# USB_to_UART.net
KiCad netlist of a schematic drawn in Altium Designer
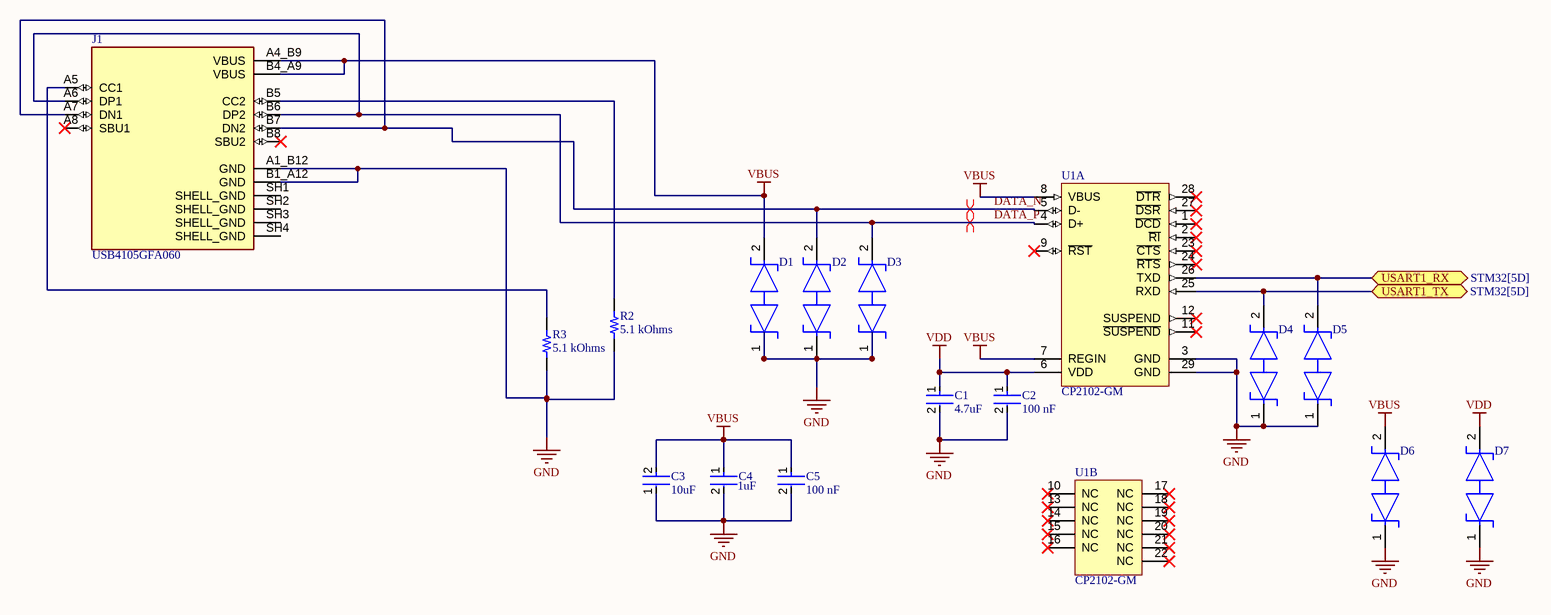
[diagram p0: USB_to_UART.SchDoc]

(export (version "E")
  (design (tool "Eeschema 10.0.6"))
  (components
    (comp (ref "C1")
      (value "4.7uF")
      (footprint "FP-C1005-050-0_15-IPC_C")
      (description "CAP CER 4.7UF 10V X5R 0402")
      (fields (field (name "TOLERANCE") "10%") (field (name "MANUFACTURER") "TDK"))
      (libsource (lib "USBUART-001") (part "b4654b650e69147ec39a6b967a45e02"))
    )
    (comp (ref "C2")
      (value "100 nF")
      (footprint "FP-CC0402-MFG")
      (description "CAP CER 0.1UF 16V X7R 0402")
      (fields (field (name "MANUFACTURER") "YAGEO") (field (name "TOLERANCE") "0.1"))
      (libsource (lib "USBUART-001") (part "11868f565c42a9108669ba33697ecf6"))
    )
    (comp (ref "C3")
      (value "10uF")
      (footprint "FP-C1608-080-0_1-MFG")
      (description "Multilayer Ceramic Capacitors 10μF ±10% 10V X5R SMD 0603")
      (fields (field (name "VOLTAGE") "10V") (field (name "TOLERANCE") "10%"))
      (libsource (lib "Altium Content Vault") (part "236180d848d6139a670b325ea6854c9"))
    )
    (comp (ref "C4")
      (value "1uF")
      (footprint "FP-C0402C105K8PACTU-MFG")
      (description "CAP CER 1UF 10V X5R 0402")
      (fields (field (name "VOLTAGE") "10V") (field (name "TOLERANCE") "10%"))
      (libsource (lib "USBUART-001") (part "11868f565c42a9108669ba33697ecf6"))
    )
    (comp (ref "C5")
      (value "100 nF")
      (footprint "FP-CC0402-MFG")
      (description "CAP CER 0.1UF 16V X7R 0402")
      (fields (field (name "MANUFACTURER") "YAGEO") (field (name "TOLERANCE") "0.1"))
      (libsource (lib "USBUART-001") (part "11868f565c42a9108669ba33697ecf6"))
    )
    (comp (ref "D1")
      (value "TPD1E10B06DPYR")
      (footprint "FP-DPY0002A-MFG")
      (description "TVS DIODE 5.5V 14V 2X1SON")
      (fields (field (name "MANUFACTURER") "Texas Instruments"))
      (libsource (lib "Altium Content Vault") (part "208e19b57522434895fa003e5d5b197"))
    )
    (comp (ref "D2")
      (value "TPD1E10B06DPYR")
      (footprint "FP-DPY0002A-MFG")
      (description "TVS DIODE 5.5V 14V 2X1SON")
      (fields (field (name "MANUFACTURER") "Texas Instruments"))
      (libsource (lib "Altium Content Vault") (part "208e19b57522434895fa003e5d5b197"))
    )
    (comp (ref "D3")
      (value "TPD1E10B06DPYR")
      (footprint "FP-DPY0002A-MFG")
      (description "TVS DIODE 5.5V 14V 2X1SON")
      (fields (field (name "MANUFACTURER") "Texas Instruments"))
      (libsource (lib "Altium Content Vault") (part "208e19b57522434895fa003e5d5b197"))
    )
    (comp (ref "D4")
      (value "TPD1E10B06DPYR")
      (footprint "FP-DPY0002A-MFG")
      (description "TVS DIODE 5.5V 14V 2X1SON")
      (fields (field (name "MANUFACTURER") "Texas Instruments"))
      (libsource (lib "Altium Content Vault") (part "208e19b57522434895fa003e5d5b197"))
    )
    (comp (ref "D5")
      (value "TPD1E10B06DPYR")
      (footprint "FP-DPY0002A-MFG")
      (description "TVS DIODE 5.5V 14V 2X1SON")
      (fields (field (name "MANUFACTURER") "Texas Instruments"))
      (libsource (lib "Altium Content Vault") (part "208e19b57522434895fa003e5d5b197"))
    )
    (comp (ref "D6")
      (value "TPD1E10B06DPYR")
      (footprint "FP-DPY0002A-MFG")
      (description "TVS DIODE 5.5V 14V 2X1SON")
      (fields (field (name "MANUFACTURER") "Texas Instruments"))
      (libsource (lib "Altium Content Vault") (part "208e19b57522434895fa003e5d5b197"))
    )
    (comp (ref "D7")
      (value "TPD1E10B06DPYR")
      (footprint "FP-DPY0002A-MFG")
      (description "TVS DIODE 5.5V 14V 2X1SON")
      (fields (field (name "MANUFACTURER") "Texas Instruments"))
      (libsource (lib "Altium Content Vault") (part "208e19b57522434895fa003e5d5b197"))
    )
    (comp (ref "J1")
      (value "USB4105GFA060")
      (footprint "GCT_USB4105GFA060")
      (fields (field (name "MF") "Global Connector Technology"))
      (libsource (lib "University of Massachusetts Lowell") (part "USB4105GFA060"))
    )
    (comp (ref "R2")
      (value "5.1 kOhms")
      (footprint "YAGEO RES 0603_1608")
      (description "RES 5.1K OHM 5% 1/10W 0603")
      (fields (field (name "PART NUMBER") "RC0603JR-105K1L"))
      (libsource (lib "University of Massachusetts Lowell") (part "RESISTOR"))
    )
    (comp (ref "R3")
      (value "5.1 kOhms")
      (footprint "YAGEO RES 0603_1608")
      (description "RES 5.1K OHM 5% 1/10W 0603")
      (fields (field (name "PART NUMBER") "RC0603JR-105K1L"))
      (libsource (lib "University of Massachusetts Lowell") (part "RESISTOR"))
    )
    (comp (ref "U1")
      (value "CP2102-GM")
      (footprint "SLAB-QFN-28-3125x3125TP_N")
      (description "Single-Chip USB to UART Bridge, 1024 Bytes EEPROM, -40 to 85 degC, 28-pin QFN, Tube")
      (fields (field (name "MANUFACTURER") "Silicon Labs"))
      (libsource (lib "USBUART-001") (part "SLAB-CP210X-QFN-28-29"))
    )
  )
  (nets
    (net (code "1") (name "/DATA_N") (class "Default")
      (node (ref "D2") (pin "2") (pinfunction "2_2") (pintype "passive"))
      (node (ref "J1") (pin "A7") (pinfunction "DN1_A7") (pintype "bidirectional"))
      (node (ref "J1") (pin "B7") (pinfunction "DN2_B7") (pintype "bidirectional"))
      (node (ref "U1") (pin "5") (pinfunction "D-_5") (pintype "bidirectional"))
    )
    (net (code "2") (name "/DATA_P") (class "Default")
      (node (ref "D3") (pin "2") (pinfunction "2_2") (pintype "passive"))
      (node (ref "J1") (pin "A6") (pinfunction "DP1_A6") (pintype "bidirectional"))
      (node (ref "J1") (pin "B6") (pinfunction "DP2_B6") (pintype "bidirectional"))
      (node (ref "U1") (pin "4") (pinfunction "D+_4") (pintype "bidirectional"))
    )
    (net (code "3") (name "/USART1_RX") (class "Default")
      (node (ref "D5") (pin "2") (pinfunction "2_2") (pintype "passive"))
      (node (ref "U1") (pin "26") (pinfunction "TXD_26") (pintype "output"))
    )
    (net (code "4") (name "/USART1_TX") (class "Default")
      (node (ref "D4") (pin "2") (pinfunction "2_2") (pintype "passive"))
      (node (ref "U1") (pin "25") (pinfunction "RXD_25") (pintype "input"))
    )
    (net (code "5") (name "GND") (class "Default")
      (node (ref "C1") (pin "2") (pinfunction "2_2") (pintype "passive"))
      (node (ref "C2") (pin "2") (pinfunction "2_2") (pintype "passive"))
      (node (ref "C3") (pin "1") (pinfunction "1_1") (pintype "passive"))
      (node (ref "C4") (pin "2") (pinfunction "2_2") (pintype "passive"))
      (node (ref "C5") (pin "2") (pinfunction "2_2") (pintype "passive"))
      (node (ref "D1") (pin "1") (pinfunction "1_1") (pintype "passive"))
      (node (ref "D2") (pin "1") (pinfunction "1_1") (pintype "passive"))
      (node (ref "D3") (pin "1") (pinfunction "1_1") (pintype "passive"))
      (node (ref "D4") (pin "1") (pinfunction "1_1") (pintype "passive"))
      (node (ref "D5") (pin "1") (pinfunction "1_1") (pintype "passive"))
      (node (ref "D6") (pin "1") (pinfunction "1_1") (pintype "passive"))
      (node (ref "D7") (pin "1") (pinfunction "1_1") (pintype "passive"))
      (node (ref "J1") (pin "A1_B12") (pinfunction "GND_A1_B12") (pintype "power_in"))
      (node (ref "J1") (pin "B1_A12") (pinfunction "GND_B1_A12") (pintype "power_in"))
      (node (ref "R2") (pin "1") (pinfunction "1_1") (pintype "passive"))
      (node (ref "R3") (pin "1") (pinfunction "1_1") (pintype "passive"))
      (node (ref "U1") (pin "29") (pinfunction "GND_29") (pintype "power_in"))
      (node (ref "U1") (pin "3") (pinfunction "GND_3") (pintype "power_in"))
    )
    (net (code "6") (name "Net-(J1-CC1)") (class "Default")
      (node (ref "J1") (pin "A5") (pinfunction "CC1_A5") (pintype "bidirectional"))
      (node (ref "R3") (pin "2") (pinfunction "2_2") (pintype "passive"))
    )
    (net (code "7") (name "Net-(J1-CC2)") (class "Default")
      (node (ref "J1") (pin "B5") (pinfunction "CC2_B5") (pintype "bidirectional"))
      (node (ref "R2") (pin "2") (pinfunction "2_2") (pintype "passive"))
    )
    (net (code "8") (name "VBUS") (class "Default")
      (node (ref "C3") (pin "2") (pinfunction "2_2") (pintype "passive"))
      (node (ref "C4") (pin "1") (pinfunction "1_1") (pintype "passive"))
      (node (ref "C5") (pin "1") (pinfunction "1_1") (pintype "passive"))
      (node (ref "D1") (pin "2") (pinfunction "2_2") (pintype "passive"))
      (node (ref "D6") (pin "2") (pinfunction "2_2") (pintype "passive"))
      (node (ref "J1") (pin "A4_B9") (pinfunction "VBUS_A4_B9") (pintype "power_in"))
      (node (ref "J1") (pin "B4_A9") (pinfunction "VBUS_B4_A9") (pintype "power_in"))
      (node (ref "U1") (pin "7") (pinfunction "REGIN_7") (pintype "power_in"))
      (node (ref "U1") (pin "8") (pinfunction "VBUS_8") (pintype "input"))
    )
    (net (code "9") (name "VDD") (class "Default")
      (node (ref "C1") (pin "1") (pinfunction "1_1") (pintype "passive"))
      (node (ref "C2") (pin "1") (pinfunction "1_1") (pintype "passive"))
      (node (ref "D7") (pin "2") (pinfunction "2_2") (pintype "passive"))
      (node (ref "U1") (pin "6") (pinfunction "VDD_6") (pintype "power_in"))
    )
    (net (code "10") (name "unconnected-(J1-SBU1-PadA8)") (class "Default")
      (node (ref "J1") (pin "A8") (pinfunction "SBU1_A8") (pintype "bidirectional+no_connect"))
    )
    (net (code "11") (name "unconnected-(J1-SBU2-PadB8)") (class "Default")
      (node (ref "J1") (pin "B8") (pinfunction "SBU2_B8") (pintype "bidirectional+no_connect"))
    )
    (net (code "12") (name "unconnected-(J1-SHELL_GND-PadSH1)") (class "Default")
      (node (ref "J1") (pin "SH1") (pinfunction "SHELL_GND_SH1") (pintype "power_in"))
    )
    (net (code "13") (name "unconnected-(J1-SHELL_GND-PadSH2)") (class "Default")
      (node (ref "J1") (pin "SH2") (pinfunction "SHELL_GND_SH2") (pintype "power_in"))
    )
    (net (code "14") (name "unconnected-(J1-SHELL_GND-PadSH3)") (class "Default")
      (node (ref "J1") (pin "SH3") (pinfunction "SHELL_GND_SH3") (pintype "power_in"))
    )
    (net (code "15") (name "unconnected-(J1-SHELL_GND-PadSH4)") (class "Default")
      (node (ref "J1") (pin "SH4") (pinfunction "SHELL_GND_SH4") (pintype "power_in"))
    )
    (net (code "16") (name "unconnected-(U1A-SUSPEND-Pad12)") (class "Default")
      (node (ref "U1") (pin "12") (pinfunction "SUSPEND_12") (pintype "output+no_connect"))
    )
    (net (code "17") (name "unconnected-(U1A-~{CTS}-Pad23)") (class "Default")
      (node (ref "U1") (pin "23") (pinfunction "~{CTS}_23") (pintype "input+no_connect"))
    )
    (net (code "18") (name "unconnected-(U1A-~{DCD}-Pad1)") (class "Default")
      (node (ref "U1") (pin "1") (pinfunction "~{DCD}_1") (pintype "input+no_connect"))
    )
    (net (code "19") (name "unconnected-(U1A-~{DSR}-Pad27)") (class "Default")
      (node (ref "U1") (pin "27") (pinfunction "~{DSR}_27") (pintype "input+no_connect"))
    )
    (net (code "20") (name "unconnected-(U1A-~{DTR}-Pad28)") (class "Default")
      (node (ref "U1") (pin "28") (pinfunction "~{DTR}_28") (pintype "output+no_connect"))
    )
    (net (code "21") (name "unconnected-(U1A-~{RI}-Pad2)") (class "Default")
      (node (ref "U1") (pin "2") (pinfunction "~{RI}_2") (pintype "input+no_connect"))
    )
    (net (code "22") (name "unconnected-(U1A-~{RST}-Pad9)") (class "Default")
      (node (ref "U1") (pin "9") (pinfunction "~{RST}_9") (pintype "bidirectional+no_connect"))
    )
    (net (code "23") (name "unconnected-(U1A-~{RTS}-Pad24)") (class "Default")
      (node (ref "U1") (pin "24") (pinfunction "~{RTS}_24") (pintype "output+no_connect"))
    )
    (net (code "24") (name "unconnected-(U1A-~{SUSPEND}-Pad11)") (class "Default")
      (node (ref "U1") (pin "11") (pinfunction "~{SUSPEND}_11") (pintype "output+no_connect"))
    )
    (net (code "25") (name "unconnected-(U1B-NC-Pad10)") (class "Default")
      (node (ref "U1") (pin "10") (pinfunction "NC_10") (pintype "passive+no_connect"))
    )
    (net (code "26") (name "unconnected-(U1B-NC-Pad13)") (class "Default")
      (node (ref "U1") (pin "13") (pinfunction "NC_13") (pintype "passive+no_connect"))
    )
    (net (code "27") (name "unconnected-(U1B-NC-Pad14)") (class "Default")
      (node (ref "U1") (pin "14") (pinfunction "NC_14") (pintype "passive+no_connect"))
    )
    (net (code "28") (name "unconnected-(U1B-NC-Pad15)") (class "Default")
      (node (ref "U1") (pin "15") (pinfunction "NC_15") (pintype "passive+no_connect"))
    )
    (net (code "29") (name "unconnected-(U1B-NC-Pad16)") (class "Default")
      (node (ref "U1") (pin "16") (pinfunction "NC_16") (pintype "passive+no_connect"))
    )
    (net (code "30") (name "unconnected-(U1B-NC-Pad17)") (class "Default")
      (node (ref "U1") (pin "17") (pinfunction "NC_17") (pintype "passive+no_connect"))
    )
    (net (code "31") (name "unconnected-(U1B-NC-Pad18)") (class "Default")
      (node (ref "U1") (pin "18") (pinfunction "NC_18") (pintype "passive+no_connect"))
    )
    (net (code "32") (name "unconnected-(U1B-NC-Pad19)") (class "Default")
      (node (ref "U1") (pin "19") (pinfunction "NC_19") (pintype "passive+no_connect"))
    )
    (net (code "33") (name "unconnected-(U1B-NC-Pad20)") (class "Default")
      (node (ref "U1") (pin "20") (pinfunction "NC_20") (pintype "passive+no_connect"))
    )
    (net (code "34") (name "unconnected-(U1B-NC-Pad21)") (class "Default")
      (node (ref "U1") (pin "21") (pinfunction "NC_21") (pintype "passive+no_connect"))
    )
    (net (code "35") (name "unconnected-(U1B-NC-Pad22)") (class "Default")
      (node (ref "U1") (pin "22") (pinfunction "NC_22") (pintype "passive+no_connect"))
    )
  )
)
